# ESC1.net
KiCad netlist of a schematic drawn in Altium Designer
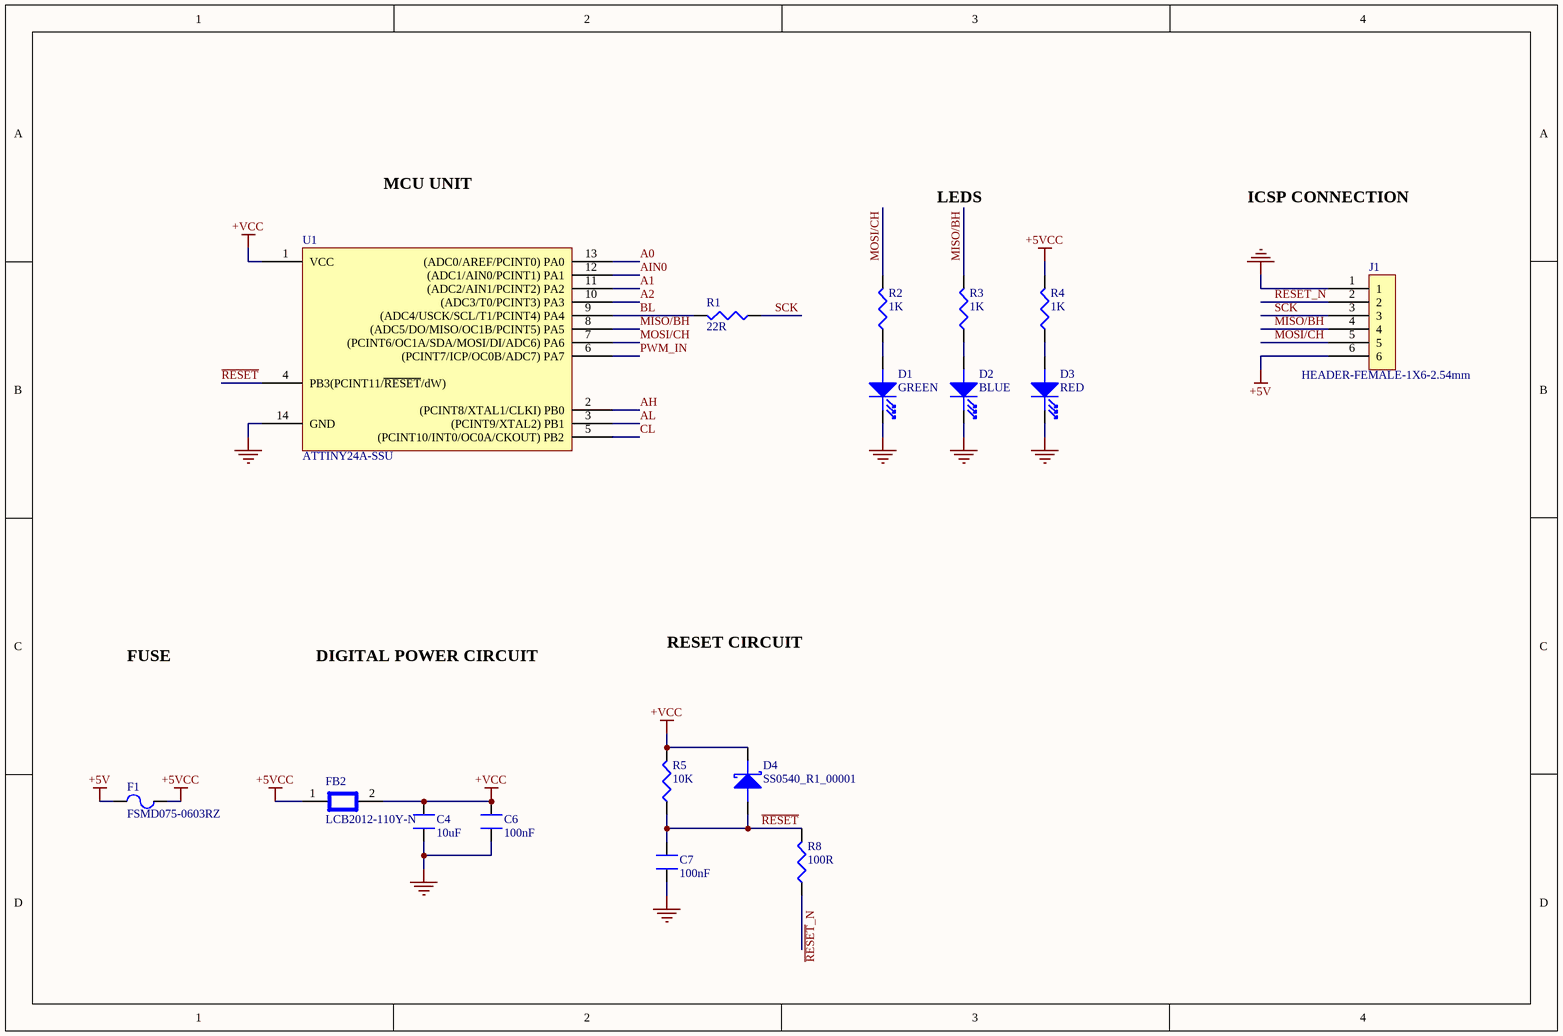
[diagram p0: ESC1.SchDoc]

(export (version "E")
  (design (tool "Eeschema 10.0.6"))
  (components
    (comp (ref "C4")
      (value "10uF")
      (footprint "Z0603")
      (description "Cap Ceramic 10uF 10V X5R 10% Pad SMD 0603 85C T/R")
      (fields
        (field (name "MANUFACTURER") "Samsung")
        (field (name "MANUFACTURER PART NUMBER") "CL10A106KP8NNNC")
      )
      (libsource (lib "ESClib1") (part "CL10A106KP8NNNC"))
    )
    (comp (ref "C6")
      (value "100nF")
      (footprint "Z0603")
      (description "Multi Layer Ceramic Capacitor (MLCC) / Cap Ceramic 0.1uF 50V X7R 10% Pad SMD 0603 125°C T/R")
      (fields
        (field (name "MANUFACTURER") "Samsung")
        (field (name "MANUFACTURER PART NUMBER") "CL10B104KB8NNNC")
      )
      (libsource (lib "ESClib1") (part "CL10B104KB8NNNC"))
    )
    (comp (ref "C7")
      (value "100nF")
      (footprint "Z0603")
      (description "Multi Layer Ceramic Capacitor (MLCC) / Cap Ceramic 0.1uF 50V X7R 10% Pad SMD 0603 125°C T/R")
      (fields
        (field (name "MANUFACTURER") "Samsung")
        (field (name "MANUFACTURER PART NUMBER") "CL10B104KB8NNNC")
      )
      (libsource (lib "ESClib1") (part "CL10B104KB8NNNC"))
    )
    (comp (ref "D1")
      (value "GREEN")
      (footprint "LED-0603")
      (libsource (lib "ESClib1") (part "HL-PST-1608U51GC"))
    )
    (comp (ref "D2")
      (value "BLUE")
      (footprint "LED-0603")
      (libsource (lib "ESClib1") (part "27-21/B7C-ZR1S1N/3C"))
    )
    (comp (ref "D3")
      (value "RED")
      (footprint "LED-0603")
      (description "0603 red led alingap 631nm-639nm water clear 18-180mcd 130d")
      (fields
        (field (name "MANUFACTURER") "Vishay Lite-On")
        (field (name "MANUFACTURER PART NUMBER") "LTST-C190KRKT")
      )
      (libsource (lib "ESClib1") (part "LTST-C190KRKT"))
    )
    (comp (ref "D4")
      (value "SS0540_R1_00001")
      (footprint "SOD-123")
      (description "Diode Schottky 40V 0.5A 2-Pin SOD-123 T/R")
      (fields (field (name "MANUFACTURER") "Pan Jit"))
      (libsource (lib "ESClib1") (part "SS0540_R1_00001"))
    )
    (comp (ref "F1")
      (value "FSMD075-0603RZ")
      (footprint "F-0603")
      (libsource (lib "ESClib1") (part "FSMD075-0603RZ"))
    )
    (comp (ref "FB2")
      (value "LCB2012-110Y-N")
      (footprint "C0805")
      (libsource (lib "ESClib1") (part "LCB2012-110Y-N"))
    )
    (comp (ref "J1")
      (value "HEADER-FEMALE-1X6-2.54mm")
      (footprint "FEMALE-1X6-2.54mm")
      (description "CONN HDR 6POS 0.1 GOLD PCB")
      (fields
        (field (name "MANUFACTURER") "Sullins")
        (field (name "MANUFACTURER PART NUMBER") "PPPC061LFBN-RC")
      )
      (libsource (lib "ESClib1") (part "PPPC061LFBN-RC"))
    )
    (comp (ref "R1")
      (value "22R")
      (footprint "Z0603")
      (description "MULTICOMP         MC0603SAF220JT5E            RESISTOR, THICK FILM, 22OHM, 100mW, 1%")
      (fields
        (field (name "MANUFACTURER") "Multicomp")
        (field (name "MANUFACTURER PART NUMBER") "MC0603SAF220JT5E")
      )
      (libsource (lib "ESClib1") (part "MC0603SAF220JT5E"))
    )
    (comp (ref "R2")
      (value "1K")
      (footprint "Z0603")
      (description "MULTICOMP - MC0603SAF1001T5E - THICK FILM RESISTOR, 1KOHM, 100mW, 1%")
      (fields
        (field (name "MANUFACTURER") "Multicomp")
        (field (name "MANUFACTURER PART NUMBER") "MC0603SAF1001T5E")
      )
      (libsource (lib "ESClib1") (part "MC0603SAF1001T5E"))
    )
    (comp (ref "R3")
      (value "1K")
      (footprint "Z0603")
      (description "MULTICOMP - MC0603SAF1001T5E - THICK FILM RESISTOR, 1KOHM, 100mW, 1%")
      (fields
        (field (name "MANUFACTURER") "Multicomp")
        (field (name "MANUFACTURER PART NUMBER") "MC0603SAF1001T5E")
      )
      (libsource (lib "ESClib1") (part "MC0603SAF1001T5E"))
    )
    (comp (ref "R4")
      (value "1K")
      (footprint "Z0603")
      (description "MULTICOMP - MC0603SAF1001T5E - THICK FILM RESISTOR, 1KOHM, 100mW, 1%")
      (fields
        (field (name "MANUFACTURER") "Multicomp")
        (field (name "MANUFACTURER PART NUMBER") "MC0603SAF1001T5E")
      )
      (libsource (lib "ESClib1") (part "MC0603SAF1001T5E"))
    )
    (comp (ref "R5") (value "10K") (footprint "Z0603") (libsource (lib "ESClib1") (part "CQ03SAF1002T5E")))
    (comp (ref "R8") (value "100R") (footprint "Z0603") (libsource (lib "ESClib1") (part "0603SAJ0101T5E")))
    (comp (ref "U1")
      (value "ATTINY24A-SSU")
      (footprint "SOIC14")
      (description "MCU 8-bit ATtiny AVR RISC 2KB Flash 2.5V/3.3V/5V 14-Pin SOIC W T/R")
      (fields
        (field (name "MANUFACTURER") "Microchip / Atmel")
        (field (name "MANUFACTURER PART NUMBER") "ATTINY24A-SSUR")
      )
      (libsource (lib "ESClib1") (part "ATTINY24A-SSUR"))
    )
  )
  (nets
    (net (code "1") (name "+5V") (class "Default")
      (node (ref "F1") (pin "1") (pinfunction "1_1") (pintype "passive"))
      (node (ref "J1") (pin "6") (pinfunction "6_6") (pintype "passive"))
    )
    (net (code "2") (name "+5VCC") (class "Default")
      (node (ref "F1") (pin "2") (pinfunction "2_2") (pintype "passive"))
      (node (ref "FB2") (pin "1") (pinfunction "1_1") (pintype "passive"))
      (node (ref "R4") (pin "2") (pinfunction "2_2") (pintype "passive"))
    )
    (net (code "3") (name "+VCC") (class "Default")
      (node (ref "C4") (pin "2") (pinfunction "2_2") (pintype "passive"))
      (node (ref "C6") (pin "2") (pinfunction "2_2") (pintype "passive"))
      (node (ref "D4") (pin "1") (pinfunction "Cathode_1") (pintype "passive"))
      (node (ref "FB2") (pin "2") (pinfunction "2_2") (pintype "passive"))
      (node (ref "R5") (pin "2") (pinfunction "2_2") (pintype "passive"))
      (node (ref "U1") (pin "1") (pinfunction "VCC_1") (pintype "passive"))
    )
    (net (code "4") (name "/A0") (class "Default")
      (node (ref "U1") (pin "13") (pinfunction "(ADC0/AREF/PCINT0)_PA0_13") (pintype "passive"))
    )
    (net (code "5") (name "/A1") (class "Default")
      (node (ref "U1") (pin "11") (pinfunction "(ADC2/AIN1/PCINT2)_PA2_11") (pintype "passive"))
    )
    (net (code "6") (name "/A2") (class "Default")
      (node (ref "U1") (pin "10") (pinfunction "(ADC3/T0/PCINT3)_PA3_10") (pintype "passive"))
    )
    (net (code "7") (name "/AH") (class "Default")
      (node (ref "U1") (pin "2") (pinfunction "(PCINT8/XTAL1/CLKI)_PB0_2") (pintype "passive"))
    )
    (net (code "8") (name "/AIN0") (class "Default")
      (node (ref "U1") (pin "12") (pinfunction "(ADC1/AIN0/PCINT1)_PA1_12") (pintype "passive"))
    )
    (net (code "9") (name "/AL") (class "Default")
      (node (ref "U1") (pin "3") (pinfunction "(PCINT9/XTAL2)_PB1_3") (pintype "passive"))
    )
    (net (code "10") (name "/BL") (class "Default")
      (node (ref "R1") (pin "2") (pinfunction "2_2") (pintype "passive"))
      (node (ref "U1") (pin "9") (pinfunction "(ADC4/USCK/SCL/T1/PCINT4)_PA4_9") (pintype "passive"))
    )
    (net (code "11") (name "/CL") (class "Default")
      (node (ref "U1") (pin "5") (pinfunction "(PCINT10/INT0/OC0A/CKOUT)_PB2_5") (pintype "passive"))
    )
    (net (code "12") (name "/MISO{slash}BH") (class "Default")
      (node (ref "J1") (pin "4") (pinfunction "4_4") (pintype "passive"))
      (node (ref "R3") (pin "2") (pinfunction "2_2") (pintype "passive"))
      (node (ref "U1") (pin "8") (pinfunction "(ADC5/DO/MISO/OC1B/PCINT5)_PA5_8") (pintype "passive"))
    )
    (net (code "13") (name "/MOSI{slash}CH") (class "Default")
      (node (ref "J1") (pin "5") (pinfunction "5_5") (pintype "passive"))
      (node (ref "R2") (pin "2") (pinfunction "2_2") (pintype "passive"))
      (node (ref "U1") (pin "7") (pinfunction "(PCINT6/OC1A/SDA/MOSI/DI/ADC6)_PA6_7") (pintype "passive"))
    )
    (net (code "14") (name "/PWM_IN") (class "Default")
      (node (ref "U1") (pin "6") (pinfunction "(PCINT7/ICP/OC0B/ADC7)_PA7_6") (pintype "passive"))
    )
    (net (code "15") (name "/SCK") (class "Default")
      (node (ref "J1") (pin "3") (pinfunction "3_3") (pintype "passive"))
      (node (ref "R1") (pin "1") (pinfunction "1_1") (pintype "passive"))
    )
    (net (code "16") (name "/~{RESET}") (class "Default")
      (node (ref "C7") (pin "2") (pinfunction "2_2") (pintype "passive"))
      (node (ref "D4") (pin "2") (pinfunction "Anode_2") (pintype "passive"))
      (node (ref "R5") (pin "1") (pinfunction "1_1") (pintype "passive"))
      (node (ref "R8") (pin "2") (pinfunction "2_2") (pintype "passive"))
      (node (ref "U1") (pin "4") (pinfunction "PB3(PCINT11/~{RESET}/dW)_4") (pintype "passive"))
    )
    (net (code "17") (name "/~{RESET}_N") (class "Default")
      (node (ref "J1") (pin "2") (pinfunction "2_2") (pintype "passive"))
      (node (ref "R8") (pin "1") (pinfunction "1_1") (pintype "passive"))
    )
    (net (code "18") (name "GND") (class "Default")
      (node (ref "C4") (pin "1") (pinfunction "1_1") (pintype "passive"))
      (node (ref "C6") (pin "1") (pinfunction "1_1") (pintype "passive"))
      (node (ref "C7") (pin "1") (pinfunction "1_1") (pintype "passive"))
      (node (ref "D1") (pin "1") (pinfunction "Cathode_1") (pintype "passive"))
      (node (ref "D2") (pin "1") (pinfunction "Cathode_1") (pintype "passive"))
      (node (ref "D3") (pin "1") (pinfunction "Cathode_1") (pintype "passive"))
      (node (ref "J1") (pin "1") (pinfunction "1_1") (pintype "passive"))
      (node (ref "U1") (pin "14") (pinfunction "GND_14") (pintype "passive"))
    )
    (net (code "19") (name "Net-(D1-Anode)") (class "Default")
      (node (ref "D1") (pin "2") (pinfunction "Anode_2") (pintype "passive"))
      (node (ref "R2") (pin "1") (pinfunction "1_1") (pintype "passive"))
    )
    (net (code "20") (name "Net-(D2-Anode)") (class "Default")
      (node (ref "D2") (pin "2") (pinfunction "Anode_2") (pintype "passive"))
      (node (ref "R3") (pin "1") (pinfunction "1_1") (pintype "passive"))
    )
    (net (code "21") (name "Net-(D3-Anode)") (class "Default")
      (node (ref "D3") (pin "2") (pinfunction "Anode_2") (pintype "passive"))
      (node (ref "R4") (pin "1") (pinfunction "1_1") (pintype "passive"))
    )
  )
)
